# Ring_4_A.net
KiCad netlist of a schematic drawn in Altium Designer
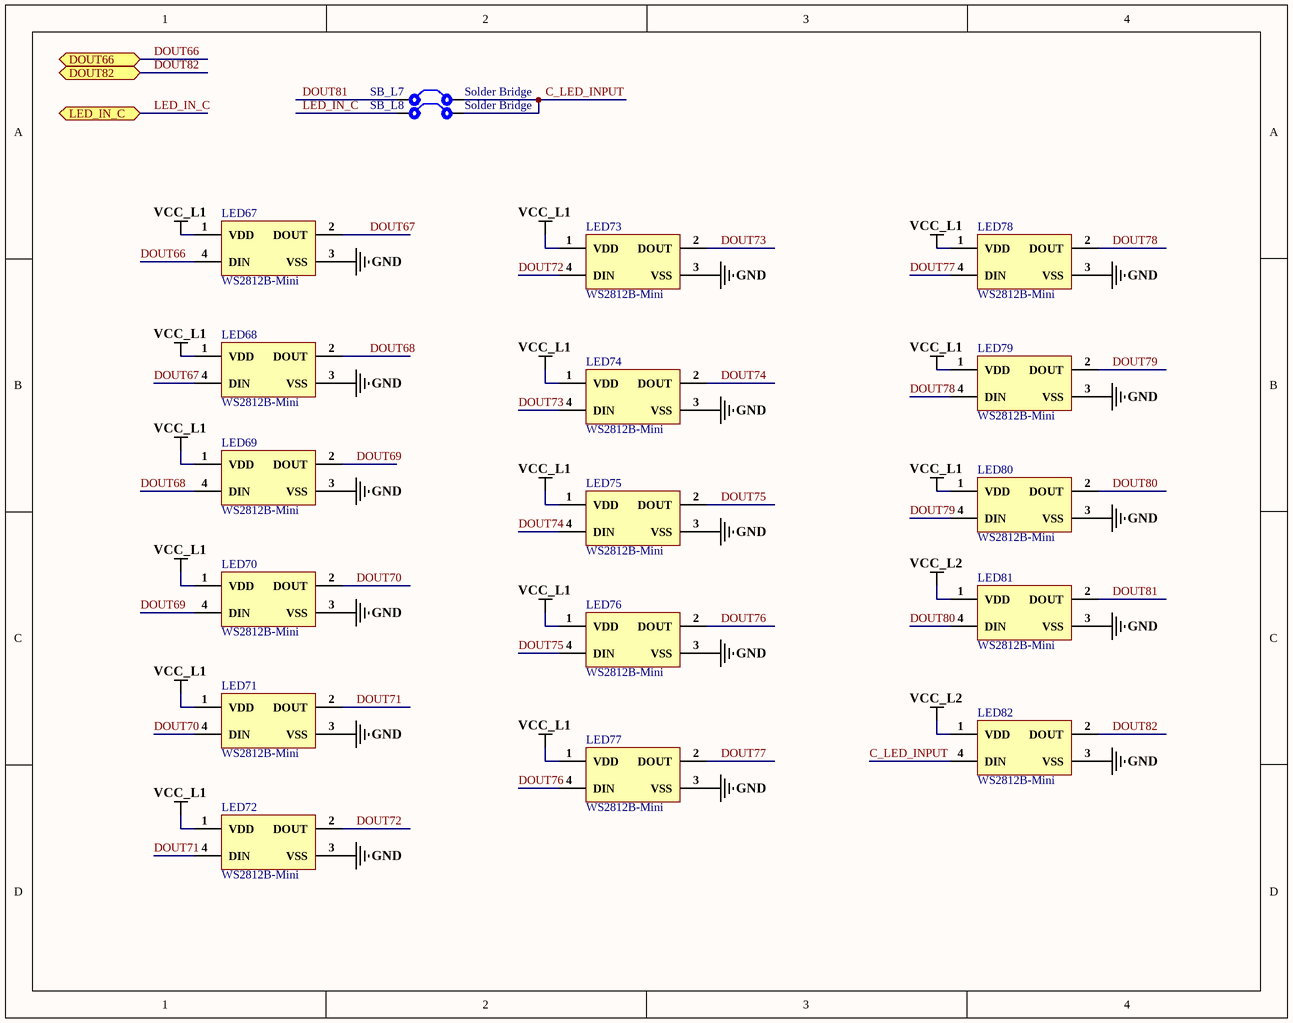
[diagram p0: Ring 4_A.SchDoc]

(export (version "E")
  (design (tool "Eeschema 10.0.6"))
  (components
    (comp (ref "LED67")
      (value "WS2812B-Mini")
      (footprint "WS2812B-Mini")
      (description "SMD,3.5x3.5mm Light Emitting Diodes (LED) RoHS")
      (fields (field (name "MANUFACTURER") "Worldsemi"))
      (libsource (lib "TT_IntLib") (part "WS2812B-Mini"))
    )
    (comp (ref "LED68")
      (value "WS2812B-Mini")
      (footprint "WS2812B-Mini")
      (description "SMD,3.5x3.5mm Light Emitting Diodes (LED) RoHS")
      (fields (field (name "MANUFACTURER") "Worldsemi"))
      (libsource (lib "TT_IntLib") (part "WS2812B-Mini"))
    )
    (comp (ref "LED69")
      (value "WS2812B-Mini")
      (footprint "WS2812B-Mini")
      (description "SMD,3.5x3.5mm Light Emitting Diodes (LED) RoHS")
      (fields (field (name "MANUFACTURER") "Worldsemi"))
      (libsource (lib "TT_IntLib") (part "WS2812B-Mini"))
    )
    (comp (ref "LED70")
      (value "WS2812B-Mini")
      (footprint "WS2812B-Mini")
      (description "SMD,3.5x3.5mm Light Emitting Diodes (LED) RoHS")
      (fields (field (name "MANUFACTURER") "Worldsemi"))
      (libsource (lib "TT_IntLib") (part "WS2812B-Mini"))
    )
    (comp (ref "LED71")
      (value "WS2812B-Mini")
      (footprint "WS2812B-Mini")
      (description "SMD,3.5x3.5mm Light Emitting Diodes (LED) RoHS")
      (fields (field (name "MANUFACTURER") "Worldsemi"))
      (libsource (lib "TT_IntLib") (part "WS2812B-Mini"))
    )
    (comp (ref "LED72")
      (value "WS2812B-Mini")
      (footprint "WS2812B-Mini")
      (description "SMD,3.5x3.5mm Light Emitting Diodes (LED) RoHS")
      (fields (field (name "MANUFACTURER") "Worldsemi"))
      (libsource (lib "TT_IntLib") (part "WS2812B-Mini"))
    )
    (comp (ref "LED73")
      (value "WS2812B-Mini")
      (footprint "WS2812B-Mini")
      (description "SMD,3.5x3.5mm Light Emitting Diodes (LED) RoHS")
      (fields (field (name "MANUFACTURER") "Worldsemi"))
      (libsource (lib "TT_IntLib") (part "WS2812B-Mini"))
    )
    (comp (ref "LED74")
      (value "WS2812B-Mini")
      (footprint "WS2812B-Mini")
      (description "SMD,3.5x3.5mm Light Emitting Diodes (LED) RoHS")
      (fields (field (name "MANUFACTURER") "Worldsemi"))
      (libsource (lib "TT_IntLib") (part "WS2812B-Mini"))
    )
    (comp (ref "LED75")
      (value "WS2812B-Mini")
      (footprint "WS2812B-Mini")
      (description "SMD,3.5x3.5mm Light Emitting Diodes (LED) RoHS")
      (fields (field (name "MANUFACTURER") "Worldsemi"))
      (libsource (lib "TT_IntLib") (part "WS2812B-Mini"))
    )
    (comp (ref "LED76")
      (value "WS2812B-Mini")
      (footprint "WS2812B-Mini")
      (description "SMD,3.5x3.5mm Light Emitting Diodes (LED) RoHS")
      (fields (field (name "MANUFACTURER") "Worldsemi"))
      (libsource (lib "TT_IntLib") (part "WS2812B-Mini"))
    )
    (comp (ref "LED77")
      (value "WS2812B-Mini")
      (footprint "WS2812B-Mini")
      (description "SMD,3.5x3.5mm Light Emitting Diodes (LED) RoHS")
      (fields (field (name "MANUFACTURER") "Worldsemi"))
      (libsource (lib "TT_IntLib") (part "WS2812B-Mini"))
    )
    (comp (ref "LED78")
      (value "WS2812B-Mini")
      (footprint "WS2812B-Mini")
      (description "SMD,3.5x3.5mm Light Emitting Diodes (LED) RoHS")
      (fields (field (name "MANUFACTURER") "Worldsemi"))
      (libsource (lib "TT_IntLib") (part "WS2812B-Mini"))
    )
    (comp (ref "LED79")
      (value "WS2812B-Mini")
      (footprint "WS2812B-Mini")
      (description "SMD,3.5x3.5mm Light Emitting Diodes (LED) RoHS")
      (fields (field (name "MANUFACTURER") "Worldsemi"))
      (libsource (lib "TT_IntLib") (part "WS2812B-Mini"))
    )
    (comp (ref "LED80")
      (value "WS2812B-Mini")
      (footprint "WS2812B-Mini")
      (description "SMD,3.5x3.5mm Light Emitting Diodes (LED) RoHS")
      (fields (field (name "MANUFACTURER") "Worldsemi"))
      (libsource (lib "TT_IntLib") (part "WS2812B-Mini"))
    )
    (comp (ref "LED81")
      (value "WS2812B-Mini")
      (footprint "WS2812B-Mini")
      (description "SMD,3.5x3.5mm Light Emitting Diodes (LED) RoHS")
      (fields (field (name "MANUFACTURER") "Worldsemi"))
      (libsource (lib "TT_IntLib") (part "WS2812B-Mini"))
    )
    (comp (ref "LED82")
      (value "WS2812B-Mini")
      (footprint "WS2812B-Mini")
      (description "SMD,3.5x3.5mm Light Emitting Diodes (LED) RoHS")
      (fields (field (name "MANUFACTURER") "Worldsemi"))
      (libsource (lib "TT_IntLib") (part "WS2812B-Mini"))
    )
    (comp (ref "SB_L7")
      (value "Solder Bridge")
      (footprint "Solder Bridge")
      (description "Solder Bridge ON")
      (libsource (lib "TT_IntLib") (part "Solder Bridge"))
    )
    (comp (ref "SB_L8")
      (value "Solder Bridge")
      (footprint "Solder Bridge")
      (description "Solder Bridge ON")
      (libsource (lib "TT_IntLib") (part "Solder Bridge"))
    )
  )
  (nets
    (net (code "1") (name "/C_LED_INPUT") (class "Default")
      (node (ref "LED82") (pin "4") (pinfunction "DIN_4") (pintype "passive"))
      (node (ref "SB_L7") (pin "2") (pinfunction "2_2") (pintype "passive"))
      (node (ref "SB_L8") (pin "2") (pinfunction "2_2") (pintype "passive"))
    )
    (net (code "2") (name "/DOUT66") (class "Default")
      (node (ref "LED67") (pin "4") (pinfunction "DIN_4") (pintype "passive"))
    )
    (net (code "3") (name "/DOUT67") (class "Default")
      (node (ref "LED67") (pin "2") (pinfunction "DOUT_2") (pintype "passive"))
      (node (ref "LED68") (pin "4") (pinfunction "DIN_4") (pintype "passive"))
    )
    (net (code "4") (name "/DOUT68") (class "Default")
      (node (ref "LED68") (pin "2") (pinfunction "DOUT_2") (pintype "passive"))
      (node (ref "LED69") (pin "4") (pinfunction "DIN_4") (pintype "passive"))
    )
    (net (code "5") (name "/DOUT69") (class "Default")
      (node (ref "LED69") (pin "2") (pinfunction "DOUT_2") (pintype "passive"))
      (node (ref "LED70") (pin "4") (pinfunction "DIN_4") (pintype "passive"))
    )
    (net (code "6") (name "/DOUT70") (class "Default")
      (node (ref "LED70") (pin "2") (pinfunction "DOUT_2") (pintype "passive"))
      (node (ref "LED71") (pin "4") (pinfunction "DIN_4") (pintype "passive"))
    )
    (net (code "7") (name "/DOUT71") (class "Default")
      (node (ref "LED71") (pin "2") (pinfunction "DOUT_2") (pintype "passive"))
      (node (ref "LED72") (pin "4") (pinfunction "DIN_4") (pintype "passive"))
    )
    (net (code "8") (name "/DOUT72") (class "Default")
      (node (ref "LED72") (pin "2") (pinfunction "DOUT_2") (pintype "passive"))
      (node (ref "LED73") (pin "4") (pinfunction "DIN_4") (pintype "passive"))
    )
    (net (code "9") (name "/DOUT73") (class "Default")
      (node (ref "LED73") (pin "2") (pinfunction "DOUT_2") (pintype "passive"))
      (node (ref "LED74") (pin "4") (pinfunction "DIN_4") (pintype "passive"))
    )
    (net (code "10") (name "/DOUT74") (class "Default")
      (node (ref "LED74") (pin "2") (pinfunction "DOUT_2") (pintype "passive"))
      (node (ref "LED75") (pin "4") (pinfunction "DIN_4") (pintype "passive"))
    )
    (net (code "11") (name "/DOUT75") (class "Default")
      (node (ref "LED75") (pin "2") (pinfunction "DOUT_2") (pintype "passive"))
      (node (ref "LED76") (pin "4") (pinfunction "DIN_4") (pintype "passive"))
    )
    (net (code "12") (name "/DOUT76") (class "Default")
      (node (ref "LED76") (pin "2") (pinfunction "DOUT_2") (pintype "passive"))
      (node (ref "LED77") (pin "4") (pinfunction "DIN_4") (pintype "passive"))
    )
    (net (code "13") (name "/DOUT77") (class "Default")
      (node (ref "LED77") (pin "2") (pinfunction "DOUT_2") (pintype "passive"))
      (node (ref "LED78") (pin "4") (pinfunction "DIN_4") (pintype "passive"))
    )
    (net (code "14") (name "/DOUT78") (class "Default")
      (node (ref "LED78") (pin "2") (pinfunction "DOUT_2") (pintype "passive"))
      (node (ref "LED79") (pin "4") (pinfunction "DIN_4") (pintype "passive"))
    )
    (net (code "15") (name "/DOUT79") (class "Default")
      (node (ref "LED79") (pin "2") (pinfunction "DOUT_2") (pintype "passive"))
      (node (ref "LED80") (pin "4") (pinfunction "DIN_4") (pintype "passive"))
    )
    (net (code "16") (name "/DOUT80") (class "Default")
      (node (ref "LED80") (pin "2") (pinfunction "DOUT_2") (pintype "passive"))
      (node (ref "LED81") (pin "4") (pinfunction "DIN_4") (pintype "passive"))
    )
    (net (code "17") (name "/DOUT81") (class "Default")
      (node (ref "LED81") (pin "2") (pinfunction "DOUT_2") (pintype "passive"))
      (node (ref "SB_L7") (pin "1") (pinfunction "1_1") (pintype "passive"))
    )
    (net (code "18") (name "/DOUT82") (class "Default")
      (node (ref "LED82") (pin "2") (pinfunction "DOUT_2") (pintype "passive"))
    )
    (net (code "19") (name "/LED_IN_C") (class "Default")
      (node (ref "SB_L8") (pin "1") (pinfunction "1_1") (pintype "passive"))
    )
    (net (code "20") (name "GND") (class "Default")
      (node (ref "LED67") (pin "3") (pinfunction "VSS_3") (pintype "passive"))
      (node (ref "LED68") (pin "3") (pinfunction "VSS_3") (pintype "passive"))
      (node (ref "LED69") (pin "3") (pinfunction "VSS_3") (pintype "passive"))
      (node (ref "LED70") (pin "3") (pinfunction "VSS_3") (pintype "passive"))
      (node (ref "LED71") (pin "3") (pinfunction "VSS_3") (pintype "passive"))
      (node (ref "LED72") (pin "3") (pinfunction "VSS_3") (pintype "passive"))
      (node (ref "LED73") (pin "3") (pinfunction "VSS_3") (pintype "passive"))
      (node (ref "LED74") (pin "3") (pinfunction "VSS_3") (pintype "passive"))
      (node (ref "LED75") (pin "3") (pinfunction "VSS_3") (pintype "passive"))
      (node (ref "LED76") (pin "3") (pinfunction "VSS_3") (pintype "passive"))
      (node (ref "LED77") (pin "3") (pinfunction "VSS_3") (pintype "passive"))
      (node (ref "LED78") (pin "3") (pinfunction "VSS_3") (pintype "passive"))
      (node (ref "LED79") (pin "3") (pinfunction "VSS_3") (pintype "passive"))
      (node (ref "LED80") (pin "3") (pinfunction "VSS_3") (pintype "passive"))
      (node (ref "LED81") (pin "3") (pinfunction "VSS_3") (pintype "passive"))
      (node (ref "LED82") (pin "3") (pinfunction "VSS_3") (pintype "passive"))
    )
    (net (code "21") (name "VCC_L1") (class "Default")
      (node (ref "LED67") (pin "1") (pinfunction "VDD_1") (pintype "passive"))
      (node (ref "LED68") (pin "1") (pinfunction "VDD_1") (pintype "passive"))
      (node (ref "LED69") (pin "1") (pinfunction "VDD_1") (pintype "passive"))
      (node (ref "LED70") (pin "1") (pinfunction "VDD_1") (pintype "passive"))
      (node (ref "LED71") (pin "1") (pinfunction "VDD_1") (pintype "passive"))
      (node (ref "LED72") (pin "1") (pinfunction "VDD_1") (pintype "passive"))
      (node (ref "LED73") (pin "1") (pinfunction "VDD_1") (pintype "passive"))
      (node (ref "LED74") (pin "1") (pinfunction "VDD_1") (pintype "passive"))
      (node (ref "LED75") (pin "1") (pinfunction "VDD_1") (pintype "passive"))
      (node (ref "LED76") (pin "1") (pinfunction "VDD_1") (pintype "passive"))
      (node (ref "LED77") (pin "1") (pinfunction "VDD_1") (pintype "passive"))
      (node (ref "LED78") (pin "1") (pinfunction "VDD_1") (pintype "passive"))
      (node (ref "LED79") (pin "1") (pinfunction "VDD_1") (pintype "passive"))
      (node (ref "LED80") (pin "1") (pinfunction "VDD_1") (pintype "passive"))
    )
    (net (code "22") (name "VCC_L2") (class "Default")
      (node (ref "LED81") (pin "1") (pinfunction "VDD_1") (pintype "passive"))
      (node (ref "LED82") (pin "1") (pinfunction "VDD_1") (pintype "passive"))
    )
  )
)
